# Scoreboard.net
KiCad netlist of a schematic drawn in Altium Designer
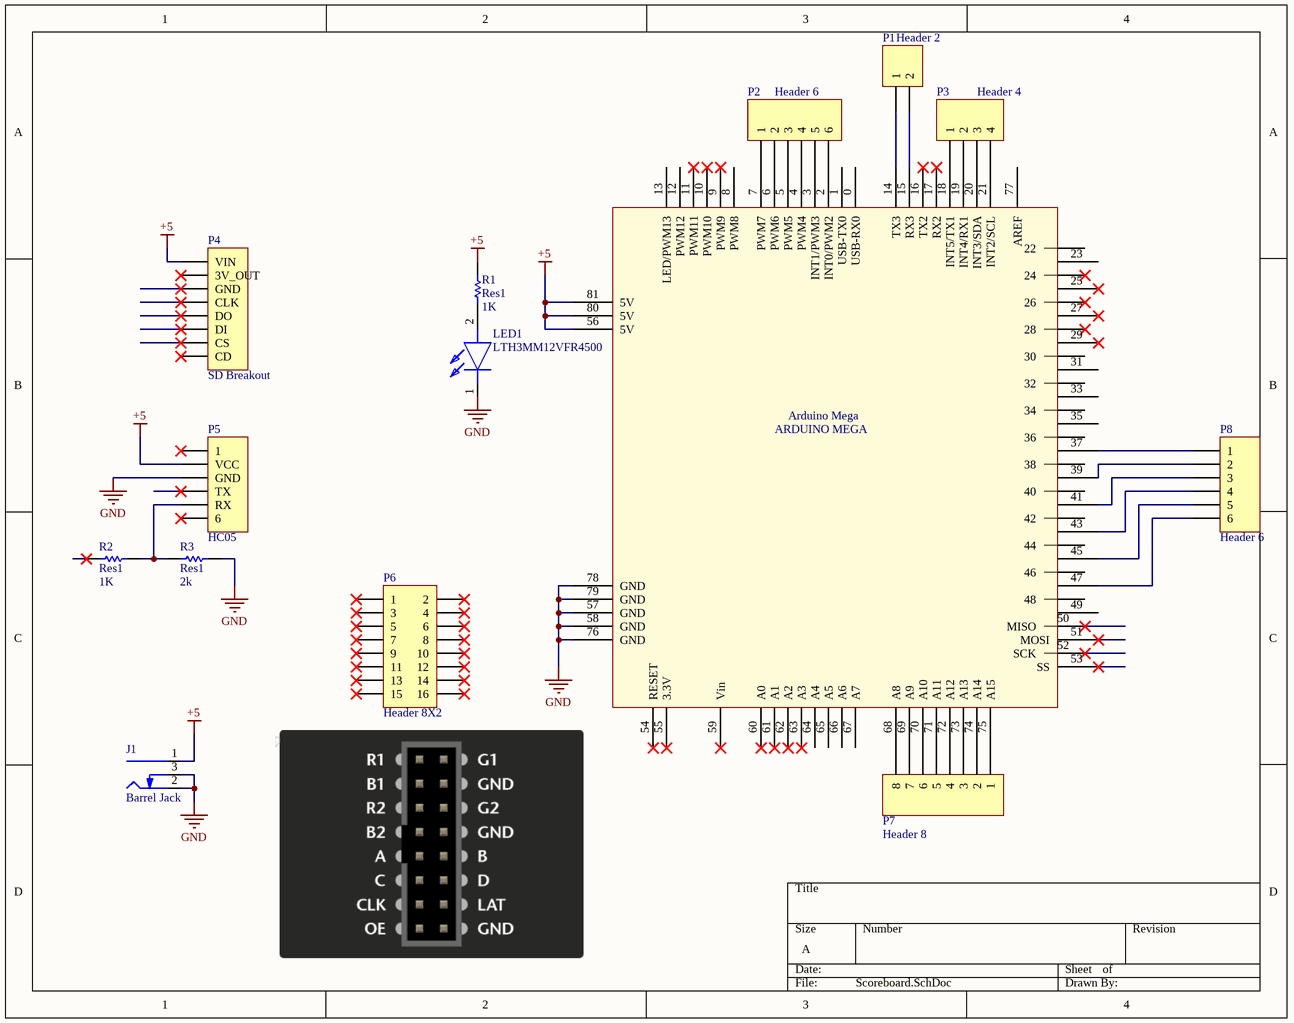
[diagram p0: Scoreboard.SchDoc]

(export (version "E")
  (design (tool "Eeschema 10.0.6"))
  (components
    (comp (ref "Arduino Mega")
      (value "ARDUINO MEGA")
      (footprint "ARDUINO MEGA")
      (libsource (lib "Arduino") (part "ARDUINO MEGA"))
    )
    (comp (ref "J1")
      (value "Barrel Jack")
      (footprint "PCB - CONNECTOR - BARREL - CUI PJ-102")
      (fields
        (field (name "ROWAN PART NUMBER") "1341")
        (field (name "MANUFACTURER") "CUI Devices")
        (field (name "MANUFACTURER PART NUMBER") "PJ-102B")
      )
      (libsource (lib "RowanAltiumLibrary") (part "SCH - CONNECTORS - BARREL CONNECTOR"))
    )
    (comp (ref "LED1")
      (value "LTH3MM12VFR4500")
      (footprint "SamacSys:LTH3MM12VFR4500")
      (description "LED RED")
      (fields (field (name "MOUSER PART NUMBER") "593-LTH3MM12VFR4500"))
      (libsource (lib "*") (part "LTH3MM12VFR4500"))
    )
    (comp (ref "P1")
      (value "Header 2")
      (footprint "HDR1X2")
      (description "Header, 2-Pin")
      (fields (field (name "PUBLISHER") "Altium Limited"))
      (libsource (lib "Miscellaneous Connectors") (part "Header 2"))
    )
    (comp (ref "P2")
      (value "Header 6")
      (footprint "HDR1X6")
      (description "Header, 6-Pin")
      (fields (field (name "PUBLISHER") "Altium Limited"))
      (libsource (lib "") (part "Header 6_2"))
    )
    (comp (ref "P3")
      (value "Header 4")
      (footprint "HDR1X4")
      (description "Header, 4-Pin")
      (fields (field (name "PUBLISHER") "Altium Limited"))
      (libsource (lib "Miscellaneous Connectors") (part "Header 4"))
    )
    (comp (ref "P4")
      (value "SD Breakout")
      (footprint "HDR1X8")
      (description "Header, 8-Pin")
      (fields (field (name "PUBLISHER") "Altium Limited"))
      (libsource (lib "Miscellaneous Connectors") (part "Header 8"))
    )
    (comp (ref "P5")
      (value "HC05")
      (footprint "HDR1X6")
      (description "Header, 6-Pin")
      (fields (field (name "PUBLISHER") "Altium Limited"))
      (libsource (lib "Miscellaneous Connectors") (part "Header 6"))
    )
    (comp (ref "P6")
      (value "Header 8X2")
      (footprint "HDR2X8")
      (description "Header, 8-Pin, Dual row")
      (fields (field (name "PUBLISHER") "Altium Limited"))
      (libsource (lib "Miscellaneous Connectors") (part "Header 8X2"))
    )
    (comp (ref "P7")
      (value "Header 8")
      (footprint "HDR1X8")
      (description "Header, 8-Pin")
      (fields (field (name "PUBLISHER") "Altium Limited"))
      (libsource (lib "") (part "Header 8_1"))
    )
    (comp (ref "P8")
      (value "Header 6")
      (footprint "HDR1X6")
      (description "Header, 6-Pin")
      (fields (field (name "PUBLISHER") "Altium Limited"))
      (libsource (lib "") (part "Header 6_1"))
    )
    (comp (ref "R1")
      (value "Res1")
      (footprint "AXIAL-0.3")
      (description "Resistor")
      (fields (field (name "ALTIUM_VALUE") "1K") (field (name "PUBLISHER") "Altium Limited"))
      (libsource (lib "Miscellaneous Devices") (part "Res1"))
    )
    (comp (ref "R2")
      (value "Res1")
      (footprint "AXIAL-0.3")
      (description "Resistor")
      (fields (field (name "ALTIUM_VALUE") "1K") (field (name "PUBLISHER") "Altium Limited"))
      (libsource (lib "Miscellaneous Devices") (part "Res1"))
    )
    (comp (ref "R3")
      (value "Res1")
      (footprint "AXIAL-0.3")
      (description "Resistor")
      (fields (field (name "ALTIUM_VALUE") "2k") (field (name "PUBLISHER") "Altium Limited"))
      (libsource (lib "Miscellaneous Devices") (part "Res1"))
    )
  )
  (nets
    (net (code "1") (name "+5") (class "Default")
      (node (ref "Arduino Mega") (pin "56") (pinfunction "5V_56") (pintype "passive"))
      (node (ref "Arduino Mega") (pin "80") (pinfunction "5V_80") (pintype "passive"))
      (node (ref "Arduino Mega") (pin "81") (pinfunction "5V_81") (pintype "passive"))
      (node (ref "J1") (pin "1") (pinfunction "Centre_1") (pintype "passive"))
      (node (ref "P4") (pin "1") (pinfunction "VIN_1") (pintype "passive"))
      (node (ref "P5") (pin "2") (pinfunction "VCC_2") (pintype "passive"))
      (node (ref "R1") (pin "2") (pinfunction "2_2") (pintype "passive"))
    )
    (net (code "2") (name "GND") (class "Default")
      (node (ref "Arduino Mega") (pin "57") (pinfunction "GND_57") (pintype "passive"))
      (node (ref "Arduino Mega") (pin "58") (pinfunction "GND_58") (pintype "passive"))
      (node (ref "Arduino Mega") (pin "76") (pinfunction "GND_76") (pintype "passive"))
      (node (ref "Arduino Mega") (pin "78") (pinfunction "GND_78") (pintype "passive"))
      (node (ref "Arduino Mega") (pin "79") (pinfunction "GND_79") (pintype "passive"))
      (node (ref "J1") (pin "2") (pinfunction "Outer_2") (pintype "passive"))
      (node (ref "J1") (pin "3") (pinfunction "SW_3") (pintype "passive"))
      (node (ref "LED1") (pin "1") (pinfunction "K_1") (pintype "passive"))
      (node (ref "P5") (pin "3") (pinfunction "GND_3") (pintype "passive"))
      (node (ref "R3") (pin "2") (pinfunction "2_2") (pintype "passive"))
    )
    (net (code "3") (name "Net-(Arduino Mega-A8)") (class "Default")
      (node (ref "Arduino Mega") (pin "68") (pinfunction "A8_68") (pintype "passive"))
      (node (ref "P7") (pin "8") (pinfunction "8_8") (pintype "passive"))
    )
    (net (code "4") (name "Net-(Arduino Mega-A9)") (class "Default")
      (node (ref "Arduino Mega") (pin "69") (pinfunction "A9_69") (pintype "passive"))
      (node (ref "P7") (pin "7") (pinfunction "7_7") (pintype "passive"))
    )
    (net (code "5") (name "Net-(Arduino Mega-A10)") (class "Default")
      (node (ref "Arduino Mega") (pin "70") (pinfunction "A10_70") (pintype "passive"))
      (node (ref "P7") (pin "6") (pinfunction "6_6") (pintype "passive"))
    )
    (net (code "6") (name "Net-(Arduino Mega-A11)") (class "Default")
      (node (ref "Arduino Mega") (pin "71") (pinfunction "A11_71") (pintype "passive"))
      (node (ref "P7") (pin "5") (pinfunction "5_5") (pintype "passive"))
    )
    (net (code "7") (name "Net-(Arduino Mega-A12)") (class "Default")
      (node (ref "Arduino Mega") (pin "72") (pinfunction "A12_72") (pintype "passive"))
      (node (ref "P7") (pin "4") (pinfunction "4_4") (pintype "passive"))
    )
    (net (code "8") (name "Net-(Arduino Mega-A13)") (class "Default")
      (node (ref "Arduino Mega") (pin "73") (pinfunction "A13_73") (pintype "passive"))
      (node (ref "P7") (pin "3") (pinfunction "3_3") (pintype "passive"))
    )
    (net (code "9") (name "Net-(Arduino Mega-A14)") (class "Default")
      (node (ref "Arduino Mega") (pin "74") (pinfunction "A14_74") (pintype "passive"))
      (node (ref "P7") (pin "2") (pinfunction "2_2") (pintype "passive"))
    )
    (net (code "10") (name "Net-(Arduino Mega-A15)") (class "Default")
      (node (ref "Arduino Mega") (pin "75") (pinfunction "A15_75") (pintype "passive"))
      (node (ref "P7") (pin "1") (pinfunction "1_1") (pintype "passive"))
    )
    (net (code "11") (name "Net-(Arduino Mega-INT0{slash}PWM2)") (class "Default")
      (node (ref "Arduino Mega") (pin "2") (pinfunction "INT0/PWM2_2") (pintype "passive"))
      (node (ref "P2") (pin "6") (pinfunction "6_6") (pintype "passive"))
    )
    (net (code "12") (name "Net-(Arduino Mega-INT1{slash}PWM3)") (class "Default")
      (node (ref "Arduino Mega") (pin "3") (pinfunction "INT1/PWM3_3") (pintype "passive"))
      (node (ref "P2") (pin "5") (pinfunction "5_5") (pintype "passive"))
    )
    (net (code "13") (name "Net-(Arduino Mega-INT2{slash}SCL)") (class "Default")
      (node (ref "Arduino Mega") (pin "21") (pinfunction "INT2/SCL_21") (pintype "passive"))
      (node (ref "P3") (pin "4") (pinfunction "4_4") (pintype "passive"))
    )
    (net (code "14") (name "Net-(Arduino Mega-INT3{slash}SDA)") (class "Default")
      (node (ref "Arduino Mega") (pin "20") (pinfunction "INT3/SDA_20") (pintype "passive"))
      (node (ref "P3") (pin "3") (pinfunction "3_3") (pintype "passive"))
    )
    (net (code "15") (name "Net-(Arduino Mega-INT4{slash}RX1)") (class "Default")
      (node (ref "Arduino Mega") (pin "19") (pinfunction "INT4/RX1_19") (pintype "passive"))
      (node (ref "P3") (pin "2") (pinfunction "2_2") (pintype "passive"))
    )
    (net (code "16") (name "Net-(Arduino Mega-INT5{slash}TX1)") (class "Default")
      (node (ref "Arduino Mega") (pin "18") (pinfunction "INT5/TX1_18") (pintype "passive"))
      (node (ref "P3") (pin "1") (pinfunction "1_1") (pintype "passive"))
    )
    (net (code "17") (name "Net-(Arduino Mega-PWM4)") (class "Default")
      (node (ref "Arduino Mega") (pin "4") (pinfunction "PWM4_4") (pintype "passive"))
      (node (ref "P2") (pin "4") (pinfunction "4_4") (pintype "passive"))
    )
    (net (code "18") (name "Net-(Arduino Mega-PWM5)") (class "Default")
      (node (ref "Arduino Mega") (pin "5") (pinfunction "PWM5_5") (pintype "passive"))
      (node (ref "P2") (pin "3") (pinfunction "3_3") (pintype "passive"))
    )
    (net (code "19") (name "Net-(Arduino Mega-PWM6)") (class "Default")
      (node (ref "Arduino Mega") (pin "6") (pinfunction "PWM6_6") (pintype "passive"))
      (node (ref "P2") (pin "2") (pinfunction "2_2") (pintype "passive"))
    )
    (net (code "20") (name "Net-(Arduino Mega-PWM7)") (class "Default")
      (node (ref "Arduino Mega") (pin "7") (pinfunction "PWM7_7") (pintype "passive"))
      (node (ref "P2") (pin "1") (pinfunction "1_1") (pintype "passive"))
    )
    (net (code "21") (name "Net-(Arduino Mega-Pad37)") (class "Default")
      (node (ref "Arduino Mega") (pin "37") (pinfunction "37_37") (pintype "passive"))
      (node (ref "P8") (pin "1") (pinfunction "1_1") (pintype "passive"))
    )
    (net (code "22") (name "Net-(Arduino Mega-Pad39)") (class "Default")
      (node (ref "Arduino Mega") (pin "39") (pinfunction "39_39") (pintype "passive"))
      (node (ref "P8") (pin "2") (pinfunction "2_2") (pintype "passive"))
    )
    (net (code "23") (name "Net-(Arduino Mega-Pad41)") (class "Default")
      (node (ref "Arduino Mega") (pin "41") (pinfunction "41_41") (pintype "passive"))
      (node (ref "P8") (pin "3") (pinfunction "3_3") (pintype "passive"))
    )
    (net (code "24") (name "Net-(Arduino Mega-Pad43)") (class "Default")
      (node (ref "Arduino Mega") (pin "43") (pinfunction "43_43") (pintype "passive"))
      (node (ref "P8") (pin "4") (pinfunction "4_4") (pintype "passive"))
    )
    (net (code "25") (name "Net-(Arduino Mega-Pad45)") (class "Default")
      (node (ref "Arduino Mega") (pin "45") (pinfunction "45_45") (pintype "passive"))
      (node (ref "P8") (pin "5") (pinfunction "5_5") (pintype "passive"))
    )
    (net (code "26") (name "Net-(Arduino Mega-Pad47)") (class "Default")
      (node (ref "Arduino Mega") (pin "47") (pinfunction "47_47") (pintype "passive"))
      (node (ref "P8") (pin "6") (pinfunction "6_6") (pintype "passive"))
    )
    (net (code "27") (name "Net-(Arduino Mega-RX3)") (class "Default")
      (node (ref "Arduino Mega") (pin "15") (pinfunction "RX3_15") (pintype "passive"))
      (node (ref "P1") (pin "2") (pinfunction "2_2") (pintype "passive"))
    )
    (net (code "28") (name "Net-(Arduino Mega-TX3)") (class "Default")
      (node (ref "Arduino Mega") (pin "14") (pinfunction "TX3_14") (pintype "passive"))
      (node (ref "P1") (pin "1") (pinfunction "1_1") (pintype "passive"))
    )
    (net (code "29") (name "Net-(LED1-A)") (class "Default")
      (node (ref "LED1") (pin "2") (pinfunction "A_2") (pintype "passive"))
      (node (ref "R1") (pin "1") (pinfunction "1_1") (pintype "passive"))
    )
    (net (code "30") (name "Net-(P5-RX)") (class "Default")
      (node (ref "P5") (pin "5") (pinfunction "RX_5") (pintype "passive"))
      (node (ref "R2") (pin "1") (pinfunction "1_1") (pintype "passive"))
      (node (ref "R3") (pin "1") (pinfunction "1_1") (pintype "passive"))
    )
    (net (code "31") (name "unconnected-(Arduino Mega-3.3V-Pad55)") (class "Default")
      (node (ref "Arduino Mega") (pin "55") (pinfunction "3.3V_55") (pintype "passive+no_connect"))
    )
    (net (code "32") (name "unconnected-(Arduino Mega-A0-Pad60)") (class "Default")
      (node (ref "Arduino Mega") (pin "60") (pinfunction "A0_60") (pintype "passive+no_connect"))
    )
    (net (code "33") (name "unconnected-(Arduino Mega-A1-Pad61)") (class "Default")
      (node (ref "Arduino Mega") (pin "61") (pinfunction "A1_61") (pintype "passive+no_connect"))
    )
    (net (code "34") (name "unconnected-(Arduino Mega-A2-Pad62)") (class "Default")
      (node (ref "Arduino Mega") (pin "62") (pinfunction "A2_62") (pintype "passive+no_connect"))
    )
    (net (code "35") (name "unconnected-(Arduino Mega-A3-Pad63)") (class "Default")
      (node (ref "Arduino Mega") (pin "63") (pinfunction "A3_63") (pintype "passive+no_connect"))
    )
    (net (code "36") (name "unconnected-(Arduino Mega-A4-Pad64)") (class "Default")
      (node (ref "Arduino Mega") (pin "64") (pinfunction "A4_64") (pintype "passive"))
    )
    (net (code "37") (name "unconnected-(Arduino Mega-A5-Pad65)") (class "Default")
      (node (ref "Arduino Mega") (pin "65") (pinfunction "A5_65") (pintype "passive"))
    )
    (net (code "38") (name "unconnected-(Arduino Mega-A6-Pad66)") (class "Default")
      (node (ref "Arduino Mega") (pin "66") (pinfunction "A6_66") (pintype "passive"))
    )
    (net (code "39") (name "unconnected-(Arduino Mega-A7-Pad67)") (class "Default")
      (node (ref "Arduino Mega") (pin "67") (pinfunction "A7_67") (pintype "passive"))
    )
    (net (code "40") (name "unconnected-(Arduino Mega-AREF-Pad77)") (class "Default")
      (node (ref "Arduino Mega") (pin "77") (pinfunction "AREF_77") (pintype "passive"))
    )
    (net (code "41") (name "unconnected-(Arduino Mega-LED{slash}PWM13-Pad13)") (class "Default")
      (node (ref "Arduino Mega") (pin "13") (pinfunction "LED/PWM13_13") (pintype "passive"))
    )
    (net (code "42") (name "unconnected-(Arduino Mega-MISO-Pad50)") (class "Default")
      (node (ref "Arduino Mega") (pin "50") (pinfunction "MISO_50") (pintype "passive+no_connect"))
    )
    (net (code "43") (name "unconnected-(Arduino Mega-MOSI-Pad51)") (class "Default")
      (node (ref "Arduino Mega") (pin "51") (pinfunction "MOSI_51") (pintype "passive+no_connect"))
    )
    (net (code "44") (name "unconnected-(Arduino Mega-PWM8-Pad8)") (class "Default")
      (node (ref "Arduino Mega") (pin "8") (pinfunction "PWM8_8") (pintype "passive"))
    )
    (net (code "45") (name "unconnected-(Arduino Mega-PWM9-Pad9)") (class "Default")
      (node (ref "Arduino Mega") (pin "9") (pinfunction "PWM9_9") (pintype "passive+no_connect"))
    )
    (net (code "46") (name "unconnected-(Arduino Mega-PWM10-Pad10)") (class "Default")
      (node (ref "Arduino Mega") (pin "10") (pinfunction "PWM10_10") (pintype "passive+no_connect"))
    )
    (net (code "47") (name "unconnected-(Arduino Mega-PWM11-Pad11)") (class "Default")
      (node (ref "Arduino Mega") (pin "11") (pinfunction "PWM11_11") (pintype "passive+no_connect"))
    )
    (net (code "48") (name "unconnected-(Arduino Mega-PWM12-Pad12)") (class "Default")
      (node (ref "Arduino Mega") (pin "12") (pinfunction "PWM12_12") (pintype "passive"))
    )
    (net (code "49") (name "unconnected-(Arduino Mega-Pad22)") (class "Default")
      (node (ref "Arduino Mega") (pin "22") (pinfunction "22_22") (pintype "passive"))
    )
    (net (code "50") (name "unconnected-(Arduino Mega-Pad23)") (class "Default")
      (node (ref "Arduino Mega") (pin "23") (pinfunction "23_23") (pintype "passive"))
    )
    (net (code "51") (name "unconnected-(Arduino Mega-Pad24)") (class "Default")
      (node (ref "Arduino Mega") (pin "24") (pinfunction "24_24") (pintype "passive+no_connect"))
    )
    (net (code "52") (name "unconnected-(Arduino Mega-Pad25)") (class "Default")
      (node (ref "Arduino Mega") (pin "25") (pinfunction "25_25") (pintype "passive+no_connect"))
    )
    (net (code "53") (name "unconnected-(Arduino Mega-Pad26)") (class "Default")
      (node (ref "Arduino Mega") (pin "26") (pinfunction "26_26") (pintype "passive+no_connect"))
    )
    (net (code "54") (name "unconnected-(Arduino Mega-Pad27)") (class "Default")
      (node (ref "Arduino Mega") (pin "27") (pinfunction "27_27") (pintype "passive+no_connect"))
    )
    (net (code "55") (name "unconnected-(Arduino Mega-Pad28)") (class "Default")
      (node (ref "Arduino Mega") (pin "28") (pinfunction "28_28") (pintype "passive+no_connect"))
    )
    (net (code "56") (name "unconnected-(Arduino Mega-Pad29)") (class "Default")
      (node (ref "Arduino Mega") (pin "29") (pinfunction "29_29") (pintype "passive+no_connect"))
    )
    (net (code "57") (name "unconnected-(Arduino Mega-Pad30)") (class "Default")
      (node (ref "Arduino Mega") (pin "30") (pinfunction "30_30") (pintype "passive"))
    )
    (net (code "58") (name "unconnected-(Arduino Mega-Pad31)") (class "Default")
      (node (ref "Arduino Mega") (pin "31") (pinfunction "31_31") (pintype "passive"))
    )
    (net (code "59") (name "unconnected-(Arduino Mega-Pad32)") (class "Default")
      (node (ref "Arduino Mega") (pin "32") (pinfunction "32_32") (pintype "passive"))
    )
    (net (code "60") (name "unconnected-(Arduino Mega-Pad33)") (class "Default")
      (node (ref "Arduino Mega") (pin "33") (pinfunction "33_33") (pintype "passive"))
    )
    (net (code "61") (name "unconnected-(Arduino Mega-Pad34)") (class "Default")
      (node (ref "Arduino Mega") (pin "34") (pinfunction "34_34") (pintype "passive"))
    )
    (net (code "62") (name "unconnected-(Arduino Mega-Pad35)") (class "Default")
      (node (ref "Arduino Mega") (pin "35") (pinfunction "35_35") (pintype "passive"))
    )
    (net (code "63") (name "unconnected-(Arduino Mega-Pad36)") (class "Default")
      (node (ref "Arduino Mega") (pin "36") (pinfunction "36_36") (pintype "passive"))
    )
    (net (code "64") (name "unconnected-(Arduino Mega-Pad38)") (class "Default")
      (node (ref "Arduino Mega") (pin "38") (pinfunction "38_38") (pintype "passive"))
    )
    (net (code "65") (name "unconnected-(Arduino Mega-Pad40)") (class "Default")
      (node (ref "Arduino Mega") (pin "40") (pinfunction "40_40") (pintype "passive"))
    )
    (net (code "66") (name "unconnected-(Arduino Mega-Pad42)") (class "Default")
      (node (ref "Arduino Mega") (pin "42") (pinfunction "42_42") (pintype "passive"))
    )
    (net (code "67") (name "unconnected-(Arduino Mega-Pad44)") (class "Default")
      (node (ref "Arduino Mega") (pin "44") (pinfunction "44_44") (pintype "passive"))
    )
    (net (code "68") (name "unconnected-(Arduino Mega-Pad46)") (class "Default")
      (node (ref "Arduino Mega") (pin "46") (pinfunction "46_46") (pintype "passive"))
    )
    (net (code "69") (name "unconnected-(Arduino Mega-Pad48)") (class "Default")
      (node (ref "Arduino Mega") (pin "48") (pinfunction "48_48") (pintype "passive"))
    )
    (net (code "70") (name "unconnected-(Arduino Mega-Pad49)") (class "Default")
      (node (ref "Arduino Mega") (pin "49") (pinfunction "49_49") (pintype "passive"))
    )
    (net (code "71") (name "unconnected-(Arduino Mega-RESET-Pad54)") (class "Default")
      (node (ref "Arduino Mega") (pin "54") (pinfunction "RESET_54") (pintype "passive+no_connect"))
    )
    (net (code "72") (name "unconnected-(Arduino Mega-RX2-Pad17)") (class "Default")
      (node (ref "Arduino Mega") (pin "17") (pinfunction "RX2_17") (pintype "passive+no_connect"))
    )
    (net (code "73") (name "unconnected-(Arduino Mega-SCK-Pad52)") (class "Default")
      (node (ref "Arduino Mega") (pin "52") (pinfunction "SCK_52") (pintype "passive+no_connect"))
    )
    (net (code "74") (name "unconnected-(Arduino Mega-SS-Pad53)") (class "Default")
      (node (ref "Arduino Mega") (pin "53") (pinfunction "SS_53") (pintype "passive+no_connect"))
    )
    (net (code "75") (name "unconnected-(Arduino Mega-TX2-Pad16)") (class "Default")
      (node (ref "Arduino Mega") (pin "16") (pinfunction "TX2_16") (pintype "passive+no_connect"))
    )
    (net (code "76") (name "unconnected-(Arduino Mega-USB-RX0-Pad0)") (class "Default")
      (node (ref "Arduino Mega") (pin "0") (pinfunction "USB-RX0_0") (pintype "passive"))
    )
    (net (code "77") (name "unconnected-(Arduino Mega-USB-TX0-Pad1)") (class "Default")
      (node (ref "Arduino Mega") (pin "1") (pinfunction "USB-TX0_1") (pintype "passive"))
    )
    (net (code "78") (name "unconnected-(Arduino Mega-Vin-Pad59)") (class "Default")
      (node (ref "Arduino Mega") (pin "59") (pinfunction "Vin_59") (pintype "passive+no_connect"))
    )
    (net (code "79") (name "unconnected-(P4-3V_OUT-Pad2)") (class "Default")
      (node (ref "P4") (pin "2") (pinfunction "3V_OUT_2") (pintype "passive+no_connect"))
    )
    (net (code "80") (name "unconnected-(P4-CD-Pad8)") (class "Default")
      (node (ref "P4") (pin "8") (pinfunction "CD_8") (pintype "passive+no_connect"))
    )
    (net (code "81") (name "unconnected-(P4-CLK-Pad4)") (class "Default")
      (node (ref "P4") (pin "4") (pinfunction "CLK_4") (pintype "passive+no_connect"))
    )
    (net (code "82") (name "unconnected-(P4-CS-Pad7)") (class "Default")
      (node (ref "P4") (pin "7") (pinfunction "CS_7") (pintype "passive+no_connect"))
    )
    (net (code "83") (name "unconnected-(P4-DI-Pad6)") (class "Default")
      (node (ref "P4") (pin "6") (pinfunction "DI_6") (pintype "passive+no_connect"))
    )
    (net (code "84") (name "unconnected-(P4-DO-Pad5)") (class "Default")
      (node (ref "P4") (pin "5") (pinfunction "DO_5") (pintype "passive+no_connect"))
    )
    (net (code "85") (name "unconnected-(P4-GND-Pad3)") (class "Default")
      (node (ref "P4") (pin "3") (pinfunction "GND_3") (pintype "passive+no_connect"))
    )
    (net (code "86") (name "unconnected-(P5-Pad1)") (class "Default")
      (node (ref "P5") (pin "1") (pinfunction "1_1") (pintype "passive+no_connect"))
    )
    (net (code "87") (name "unconnected-(P5-Pad6)") (class "Default")
      (node (ref "P5") (pin "6") (pinfunction "6_6") (pintype "passive+no_connect"))
    )
    (net (code "88") (name "unconnected-(P5-TX-Pad4)") (class "Default")
      (node (ref "P5") (pin "4") (pinfunction "TX_4") (pintype "passive+no_connect"))
    )
    (net (code "89") (name "unconnected-(P6-Pad1)") (class "Default")
      (node (ref "P6") (pin "1") (pinfunction "1_1") (pintype "passive+no_connect"))
    )
    (net (code "90") (name "unconnected-(P6-Pad2)") (class "Default")
      (node (ref "P6") (pin "2") (pinfunction "2_2") (pintype "passive+no_connect"))
    )
    (net (code "91") (name "unconnected-(P6-Pad3)") (class "Default")
      (node (ref "P6") (pin "3") (pinfunction "3_3") (pintype "passive+no_connect"))
    )
    (net (code "92") (name "unconnected-(P6-Pad4)") (class "Default")
      (node (ref "P6") (pin "4") (pinfunction "4_4") (pintype "passive+no_connect"))
    )
    (net (code "93") (name "unconnected-(P6-Pad5)") (class "Default")
      (node (ref "P6") (pin "5") (pinfunction "5_5") (pintype "passive+no_connect"))
    )
    (net (code "94") (name "unconnected-(P6-Pad6)") (class "Default")
      (node (ref "P6") (pin "6") (pinfunction "6_6") (pintype "passive+no_connect"))
    )
    (net (code "95") (name "unconnected-(P6-Pad7)") (class "Default")
      (node (ref "P6") (pin "7") (pinfunction "7_7") (pintype "passive+no_connect"))
    )
    (net (code "96") (name "unconnected-(P6-Pad8)") (class "Default")
      (node (ref "P6") (pin "8") (pinfunction "8_8") (pintype "passive+no_connect"))
    )
    (net (code "97") (name "unconnected-(P6-Pad9)") (class "Default")
      (node (ref "P6") (pin "9") (pinfunction "9_9") (pintype "passive+no_connect"))
    )
    (net (code "98") (name "unconnected-(P6-Pad10)") (class "Default")
      (node (ref "P6") (pin "10") (pinfunction "10_10") (pintype "passive+no_connect"))
    )
    (net (code "99") (name "unconnected-(P6-Pad11)") (class "Default")
      (node (ref "P6") (pin "11") (pinfunction "11_11") (pintype "passive+no_connect"))
    )
    (net (code "100") (name "unconnected-(P6-Pad12)") (class "Default")
      (node (ref "P6") (pin "12") (pinfunction "12_12") (pintype "passive+no_connect"))
    )
    (net (code "101") (name "unconnected-(P6-Pad13)") (class "Default")
      (node (ref "P6") (pin "13") (pinfunction "13_13") (pintype "passive+no_connect"))
    )
    (net (code "102") (name "unconnected-(P6-Pad14)") (class "Default")
      (node (ref "P6") (pin "14") (pinfunction "14_14") (pintype "passive+no_connect"))
    )
    (net (code "103") (name "unconnected-(P6-Pad15)") (class "Default")
      (node (ref "P6") (pin "15") (pinfunction "15_15") (pintype "passive+no_connect"))
    )
    (net (code "104") (name "unconnected-(P6-Pad16)") (class "Default")
      (node (ref "P6") (pin "16") (pinfunction "16_16") (pintype "passive+no_connect"))
    )
    (net (code "105") (name "unconnected-(R2-Pad2)") (class "Default")
      (node (ref "R2") (pin "2") (pinfunction "2_2") (pintype "passive+no_connect"))
    )
  )
)
